# Spartan6-Power.net
KiCad netlist of a schematic drawn in Altium Designer
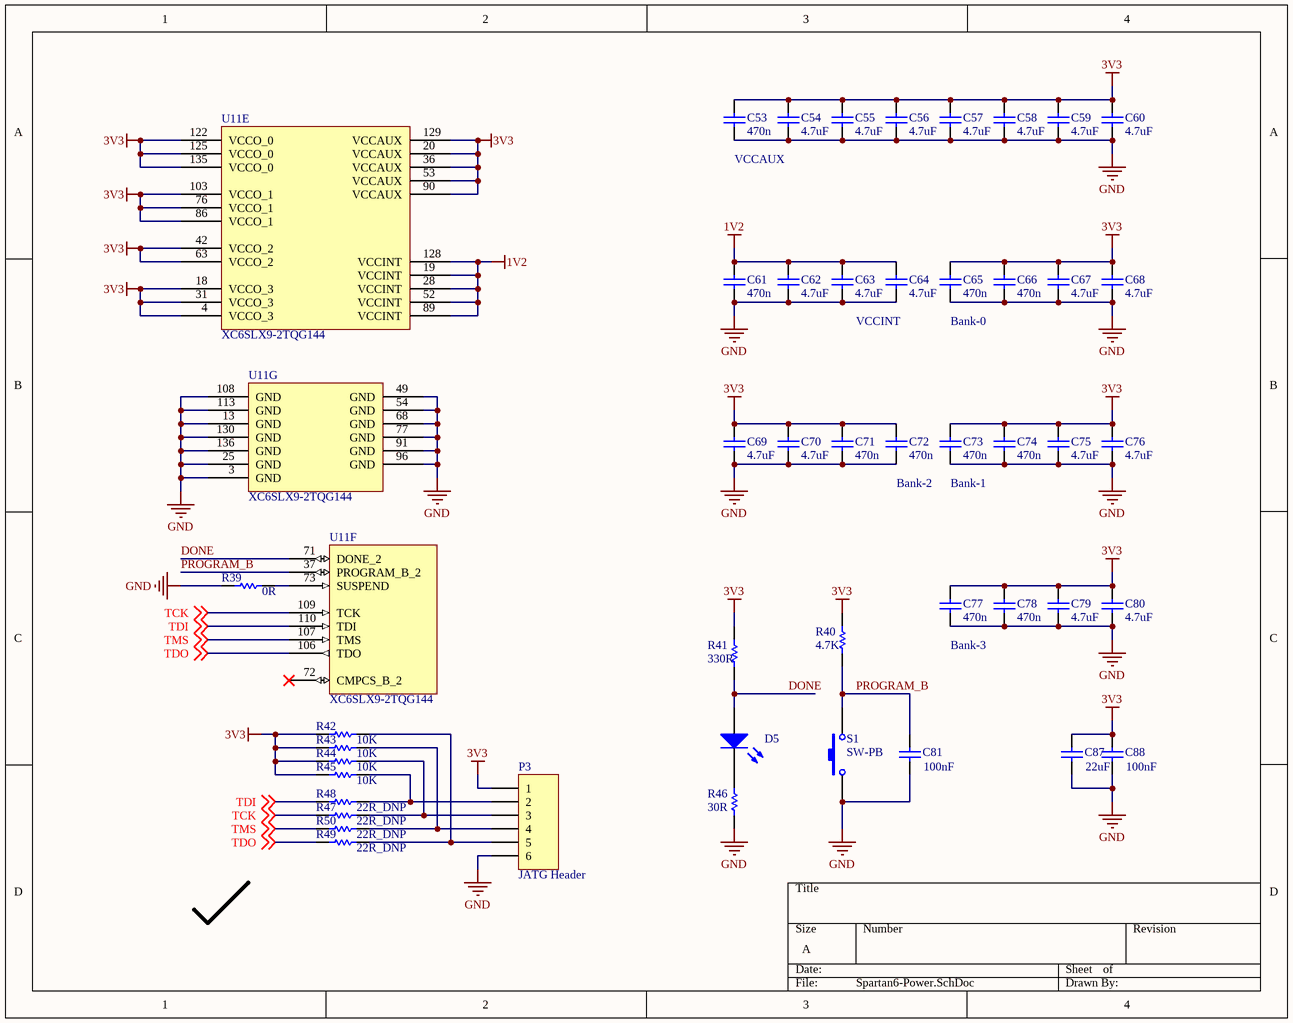
[diagram p0: Spartan6-Power.SchDoc]

(export (version "E")
  (design (tool "Eeschema 10.0.6"))
  (components
    (comp (ref "C53")
      (value "470n")
      (footprint "0402")
      (description "Capacitor (Semiconductor SIM Model)")
      (fields (field (name "Comment") "Cap Semi") (field (name "PUBLISHER") "Altium Limited"))
      (libsource (lib "Miscellaneous Devices") (part "Cap Semi"))
    )
    (comp (ref "C54")
      (value "4.7uF")
      (footprint "0603PKG")
      (description "Capacitor (Semiconductor SIM Model)")
      (fields (field (name "Comment") "Cap Semi") (field (name "PUBLISHER") "Altium Limited"))
      (libsource (lib "Miscellaneous Devices") (part "Cap Semi"))
    )
    (comp (ref "C55")
      (value "4.7uF")
      (footprint "0603PKG")
      (description "Capacitor (Semiconductor SIM Model)")
      (fields (field (name "Comment") "Cap Semi") (field (name "PUBLISHER") "Altium Limited"))
      (libsource (lib "Miscellaneous Devices") (part "Cap Semi"))
    )
    (comp (ref "C56")
      (value "4.7uF")
      (footprint "0603PKG")
      (description "Capacitor (Semiconductor SIM Model)")
      (fields (field (name "Comment") "Cap Semi") (field (name "PUBLISHER") "Altium Limited"))
      (libsource (lib "Miscellaneous Devices") (part "Cap Semi"))
    )
    (comp (ref "C57")
      (value "4.7uF")
      (footprint "0603PKG")
      (description "Capacitor (Semiconductor SIM Model)")
      (fields (field (name "Comment") "Cap Semi") (field (name "PUBLISHER") "Altium Limited"))
      (libsource (lib "Miscellaneous Devices") (part "Cap Semi"))
    )
    (comp (ref "C58")
      (value "4.7uF")
      (footprint "0603PKG")
      (description "Capacitor (Semiconductor SIM Model)")
      (fields (field (name "Comment") "Cap Semi") (field (name "PUBLISHER") "Altium Limited"))
      (libsource (lib "Miscellaneous Devices") (part "Cap Semi"))
    )
    (comp (ref "C59")
      (value "4.7uF")
      (footprint "0603PKG")
      (description "Capacitor (Semiconductor SIM Model)")
      (fields (field (name "Comment") "Cap Semi") (field (name "PUBLISHER") "Altium Limited"))
      (libsource (lib "Miscellaneous Devices") (part "Cap Semi"))
    )
    (comp (ref "C60")
      (value "4.7uF")
      (footprint "0603PKG")
      (description "Capacitor (Semiconductor SIM Model)")
      (fields (field (name "Comment") "Cap Semi") (field (name "PUBLISHER") "Altium Limited"))
      (libsource (lib "Miscellaneous Devices") (part "Cap Semi"))
    )
    (comp (ref "C61")
      (value "470n")
      (footprint "0402")
      (description "Capacitor (Semiconductor SIM Model)")
      (fields (field (name "Comment") "Cap Semi") (field (name "PUBLISHER") "Altium Limited"))
      (libsource (lib "Miscellaneous Devices") (part "Cap Semi"))
    )
    (comp (ref "C62")
      (value "4.7uF")
      (footprint "0603PKG")
      (description "Capacitor (Semiconductor SIM Model)")
      (fields (field (name "Comment") "Cap Semi") (field (name "PUBLISHER") "Altium Limited"))
      (libsource (lib "Miscellaneous Devices") (part "Cap Semi"))
    )
    (comp (ref "C63")
      (value "4.7uF")
      (footprint "0603PKG")
      (description "Capacitor (Semiconductor SIM Model)")
      (fields (field (name "Comment") "Cap Semi") (field (name "PUBLISHER") "Altium Limited"))
      (libsource (lib "Miscellaneous Devices") (part "Cap Semi"))
    )
    (comp (ref "C64")
      (value "4.7uF")
      (footprint "0603PKG")
      (description "Capacitor (Semiconductor SIM Model)")
      (fields (field (name "Comment") "Cap Semi") (field (name "PUBLISHER") "Altium Limited"))
      (libsource (lib "Miscellaneous Devices") (part "Cap Semi"))
    )
    (comp (ref "C65")
      (value "470n")
      (footprint "0402")
      (description "Capacitor (Semiconductor SIM Model)")
      (fields (field (name "Comment") "Cap Semi") (field (name "PUBLISHER") "Altium Limited"))
      (libsource (lib "Miscellaneous Devices") (part "Cap Semi"))
    )
    (comp (ref "C66")
      (value "470n")
      (footprint "0402")
      (description "Capacitor (Semiconductor SIM Model)")
      (fields (field (name "Comment") "Cap Semi") (field (name "PUBLISHER") "Altium Limited"))
      (libsource (lib "Miscellaneous Devices") (part "Cap Semi"))
    )
    (comp (ref "C67")
      (value "4.7uF")
      (footprint "0603PKG")
      (description "Capacitor (Semiconductor SIM Model)")
      (fields (field (name "Comment") "Cap Semi") (field (name "PUBLISHER") "Altium Limited"))
      (libsource (lib "Miscellaneous Devices") (part "Cap Semi"))
    )
    (comp (ref "C68")
      (value "4.7uF")
      (footprint "0603PKG")
      (description "Capacitor (Semiconductor SIM Model)")
      (fields (field (name "Comment") "Cap Semi") (field (name "PUBLISHER") "Altium Limited"))
      (libsource (lib "Miscellaneous Devices") (part "Cap Semi"))
    )
    (comp (ref "C69")
      (value "4.7uF")
      (footprint "0603PKG")
      (description "Capacitor (Semiconductor SIM Model)")
      (fields (field (name "Comment") "Cap Semi") (field (name "PUBLISHER") "Altium Limited"))
      (libsource (lib "Miscellaneous Devices") (part "Cap Semi"))
    )
    (comp (ref "C70")
      (value "4.7uF")
      (footprint "0603PKG")
      (description "Capacitor (Semiconductor SIM Model)")
      (fields (field (name "Comment") "Cap Semi") (field (name "PUBLISHER") "Altium Limited"))
      (libsource (lib "Miscellaneous Devices") (part "Cap Semi"))
    )
    (comp (ref "C71")
      (value "470n")
      (footprint "0402")
      (description "Capacitor (Semiconductor SIM Model)")
      (fields (field (name "Comment") "Cap Semi") (field (name "PUBLISHER") "Altium Limited"))
      (libsource (lib "Miscellaneous Devices") (part "Cap Semi"))
    )
    (comp (ref "C72")
      (value "470n")
      (footprint "0402")
      (description "Capacitor (Semiconductor SIM Model)")
      (fields (field (name "Comment") "Cap Semi") (field (name "PUBLISHER") "Altium Limited"))
      (libsource (lib "Miscellaneous Devices") (part "Cap Semi"))
    )
    (comp (ref "C73")
      (value "470n")
      (footprint "0402")
      (description "Capacitor (Semiconductor SIM Model)")
      (fields (field (name "Comment") "Cap Semi") (field (name "PUBLISHER") "Altium Limited"))
      (libsource (lib "Miscellaneous Devices") (part "Cap Semi"))
    )
    (comp (ref "C74")
      (value "470n")
      (footprint "0402")
      (description "Capacitor (Semiconductor SIM Model)")
      (fields (field (name "Comment") "Cap Semi") (field (name "PUBLISHER") "Altium Limited"))
      (libsource (lib "Miscellaneous Devices") (part "Cap Semi"))
    )
    (comp (ref "C75")
      (value "4.7uF")
      (footprint "0603PKG")
      (description "Capacitor (Semiconductor SIM Model)")
      (fields (field (name "Comment") "Cap Semi") (field (name "PUBLISHER") "Altium Limited"))
      (libsource (lib "Miscellaneous Devices") (part "Cap Semi"))
    )
    (comp (ref "C76")
      (value "4.7uF")
      (footprint "0603PKG")
      (description "Capacitor (Semiconductor SIM Model)")
      (fields (field (name "Comment") "Cap Semi") (field (name "PUBLISHER") "Altium Limited"))
      (libsource (lib "Miscellaneous Devices") (part "Cap Semi"))
    )
    (comp (ref "C77")
      (value "470n")
      (footprint "0402")
      (description "Capacitor (Semiconductor SIM Model)")
      (fields (field (name "Comment") "Cap Semi") (field (name "PUBLISHER") "Altium Limited"))
      (libsource (lib "Miscellaneous Devices") (part "Cap Semi"))
    )
    (comp (ref "C78")
      (value "470n")
      (footprint "0402")
      (description "Capacitor (Semiconductor SIM Model)")
      (fields (field (name "Comment") "Cap Semi") (field (name "PUBLISHER") "Altium Limited"))
      (libsource (lib "Miscellaneous Devices") (part "Cap Semi"))
    )
    (comp (ref "C79")
      (value "4.7uF")
      (footprint "0603PKG")
      (description "Capacitor (Semiconductor SIM Model)")
      (fields (field (name "Comment") "Cap Semi") (field (name "PUBLISHER") "Altium Limited"))
      (libsource (lib "Miscellaneous Devices") (part "Cap Semi"))
    )
    (comp (ref "C80")
      (value "4.7uF")
      (footprint "0603PKG")
      (description "Capacitor (Semiconductor SIM Model)")
      (fields (field (name "Comment") "Cap Semi") (field (name "PUBLISHER") "Altium Limited"))
      (libsource (lib "Miscellaneous Devices") (part "Cap Semi"))
    )
    (comp (ref "C81")
      (value "100nF")
      (footprint "C0805")
      (description "Capacitor")
      (fields (field (name "Comment") "Cap") (field (name "PUBLISHER") "Altium Limited"))
      (libsource (lib "Miscellaneous Devices") (part "Cap"))
    )
    (comp (ref "C87")
      (value "22uF")
      (footprint "C1206")
      (description "Capacitor")
      (fields (field (name "Comment") "Cap") (field (name "PUBLISHER") "Altium Limited"))
      (libsource (lib "Miscellaneous Devices") (part "Cap"))
    )
    (comp (ref "C88")
      (value "100nF")
      (footprint "C0805")
      (description "Capacitor")
      (fields (field (name "Comment") "Cap") (field (name "PUBLISHER") "Altium Limited"))
      (libsource (lib "Miscellaneous Devices") (part "Cap"))
    )
    (comp (ref "D5")
      (value "LED0")
      (footprint "C0805")
      (description "Typical INFRARED GaAs LED")
      (fields (field (name "PUBLISHER") "Altium Limited"))
      (libsource (lib "Miscellaneous Devices") (part "LED0"))
    )
    (comp (ref "P3")
      (value "JATG Header")
      (footprint "HDR1X6")
      (description "Header, 6-Pin")
      (fields (field (name "PUBLISHER") "Altium Limited"))
      (libsource (lib "Miscellaneous Connectors") (part "Header 6"))
    )
    (comp (ref "R39")
      (value "0R")
      (footprint "0603PKG")
      (description "Resistor")
      (fields (field (name "Comment") "Res1") (field (name "PUBLISHER") "Altium Limited"))
      (libsource (lib "Miscellaneous Devices") (part "Res1"))
    )
    (comp (ref "R40")
      (value "4.7K")
      (footprint "0603PKG")
      (description "Resistor")
      (fields (field (name "Comment") "Res1") (field (name "PUBLISHER") "Altium Limited"))
      (libsource (lib "Miscellaneous Devices") (part "Res1"))
    )
    (comp (ref "R41")
      (value "330R")
      (footprint "0603PKG")
      (description "Resistor")
      (fields (field (name "Comment") "Res1") (field (name "PUBLISHER") "Altium Limited"))
      (libsource (lib "Miscellaneous Devices") (part "Res1"))
    )
    (comp (ref "R42")
      (value "10K")
      (footprint "0603PKG")
      (description "Semiconductor Resistor")
      (fields (field (name "Comment") "Res Semi") (field (name "PUBLISHER") "Altium Limited"))
      (libsource (lib "Miscellaneous Devices") (part "Res Semi"))
    )
    (comp (ref "R43")
      (value "10K")
      (footprint "0603PKG")
      (description "Semiconductor Resistor")
      (fields (field (name "Comment") "Res Semi") (field (name "PUBLISHER") "Altium Limited"))
      (libsource (lib "Miscellaneous Devices") (part "Res Semi"))
    )
    (comp (ref "R44")
      (value "10K")
      (footprint "0603PKG")
      (description "Semiconductor Resistor")
      (fields (field (name "Comment") "Res Semi") (field (name "PUBLISHER") "Altium Limited"))
      (libsource (lib "Miscellaneous Devices") (part "Res Semi"))
    )
    (comp (ref "R45")
      (value "10K")
      (footprint "0603PKG")
      (description "Semiconductor Resistor")
      (fields (field (name "Comment") "Res Semi") (field (name "PUBLISHER") "Altium Limited"))
      (libsource (lib "Miscellaneous Devices") (part "Res Semi"))
    )
    (comp (ref "R46")
      (value "30R")
      (footprint "0603PKG")
      (description "Resistor")
      (fields (field (name "Comment") "Res1") (field (name "PUBLISHER") "Altium Limited"))
      (libsource (lib "Miscellaneous Devices") (part "Res1"))
    )
    (comp (ref "R47")
      (value "22R_DNP")
      (footprint "0603PKG")
      (description "Semiconductor Resistor")
      (fields (field (name "Comment") "Res Semi") (field (name "PUBLISHER") "Altium Limited"))
      (libsource (lib "Miscellaneous Devices") (part "Res Semi"))
    )
    (comp (ref "R48")
      (value "22R_DNP")
      (footprint "0603PKG")
      (description "Semiconductor Resistor")
      (fields (field (name "Comment") "Res Semi") (field (name "PUBLISHER") "Altium Limited"))
      (libsource (lib "Miscellaneous Devices") (part "Res Semi"))
    )
    (comp (ref "R49")
      (value "22R_DNP")
      (footprint "0603PKG")
      (description "Semiconductor Resistor")
      (fields (field (name "Comment") "Res Semi") (field (name "PUBLISHER") "Altium Limited"))
      (libsource (lib "Miscellaneous Devices") (part "Res Semi"))
    )
    (comp (ref "R50")
      (value "22R_DNP")
      (footprint "0603PKG")
      (description "Semiconductor Resistor")
      (fields (field (name "Comment") "Res Semi") (field (name "PUBLISHER") "Altium Limited"))
      (libsource (lib "Miscellaneous Devices") (part "Res Semi"))
    )
    (comp (ref "S1")
      (value "SW-PB")
      (footprint "SMD push button")
      (description "Switch")
      (fields (field (name "PUBLISHER") "Altium Limited"))
      (libsource (lib "Miscellaneous Devices") (part "SW-PB"))
    )
    (comp (ref "U11")
      (value "XC6SLX9-2TQG144")
      (footprint "TQG144")
      (description "Xilinx Spartan6 LX9")
      (libsource (lib "Connector_IntLib") (part "XC6SLX9-2TQG144C"))
    )
  )
  (nets
    (net (code "1") (name "/DONE") (class "Default")
      (node (ref "D5") (pin "1") (pinfunction "A_1") (pintype "passive"))
      (node (ref "R41") (pin "1") (pinfunction "1_1") (pintype "passive"))
      (node (ref "U11") (pin "71") (pinfunction "DONE_2_71") (pintype "bidirectional"))
    )
    (net (code "2") (name "/PROGRAM_B") (class "Default")
      (node (ref "C81") (pin "2") (pinfunction "2_2") (pintype "passive"))
      (node (ref "R40") (pin "1") (pinfunction "1_1") (pintype "passive"))
      (node (ref "S1") (pin "2") (pinfunction "2_2") (pintype "passive"))
      (node (ref "U11") (pin "37") (pinfunction "PROGRAM_B_2_37") (pintype "bidirectional"))
    )
    (net (code "3") (name "1V2") (class "Default")
      (node (ref "C61") (pin "1") (pinfunction "1_1") (pintype "passive"))
      (node (ref "C62") (pin "1") (pinfunction "1_1") (pintype "passive"))
      (node (ref "C63") (pin "1") (pinfunction "1_1") (pintype "passive"))
      (node (ref "C64") (pin "1") (pinfunction "1_1") (pintype "passive"))
      (node (ref "U11") (pin "128") (pinfunction "VCCINT_128") (pintype "power_in"))
      (node (ref "U11") (pin "19") (pinfunction "VCCINT_19") (pintype "power_in"))
      (node (ref "U11") (pin "28") (pinfunction "VCCINT_28") (pintype "power_in"))
      (node (ref "U11") (pin "52") (pinfunction "VCCINT_52") (pintype "power_in"))
      (node (ref "U11") (pin "89") (pinfunction "VCCINT_89") (pintype "power_in"))
    )
    (net (code "4") (name "3V3") (class "Default")
      (node (ref "C53") (pin "1") (pinfunction "1_1") (pintype "passive"))
      (node (ref "C54") (pin "1") (pinfunction "1_1") (pintype "passive"))
      (node (ref "C55") (pin "1") (pinfunction "1_1") (pintype "passive"))
      (node (ref "C56") (pin "1") (pinfunction "1_1") (pintype "passive"))
      (node (ref "C57") (pin "1") (pinfunction "1_1") (pintype "passive"))
      (node (ref "C58") (pin "1") (pinfunction "1_1") (pintype "passive"))
      (node (ref "C59") (pin "1") (pinfunction "1_1") (pintype "passive"))
      (node (ref "C60") (pin "1") (pinfunction "1_1") (pintype "passive"))
      (node (ref "C65") (pin "1") (pinfunction "1_1") (pintype "passive"))
      (node (ref "C66") (pin "1") (pinfunction "1_1") (pintype "passive"))
      (node (ref "C67") (pin "1") (pinfunction "1_1") (pintype "passive"))
      (node (ref "C68") (pin "1") (pinfunction "1_1") (pintype "passive"))
      (node (ref "C69") (pin "1") (pinfunction "1_1") (pintype "passive"))
      (node (ref "C70") (pin "1") (pinfunction "1_1") (pintype "passive"))
      (node (ref "C71") (pin "1") (pinfunction "1_1") (pintype "passive"))
      (node (ref "C72") (pin "1") (pinfunction "1_1") (pintype "passive"))
      (node (ref "C73") (pin "1") (pinfunction "1_1") (pintype "passive"))
      (node (ref "C74") (pin "1") (pinfunction "1_1") (pintype "passive"))
      (node (ref "C75") (pin "1") (pinfunction "1_1") (pintype "passive"))
      (node (ref "C76") (pin "1") (pinfunction "1_1") (pintype "passive"))
      (node (ref "C77") (pin "1") (pinfunction "1_1") (pintype "passive"))
      (node (ref "C78") (pin "1") (pinfunction "1_1") (pintype "passive"))
      (node (ref "C79") (pin "1") (pinfunction "1_1") (pintype "passive"))
      (node (ref "C80") (pin "1") (pinfunction "1_1") (pintype "passive"))
      (node (ref "C87") (pin "2") (pinfunction "2_2") (pintype "passive"))
      (node (ref "C88") (pin "2") (pinfunction "2_2") (pintype "passive"))
      (node (ref "P3") (pin "1") (pinfunction "1_1") (pintype "passive"))
      (node (ref "R40") (pin "2") (pinfunction "2_2") (pintype "passive"))
      (node (ref "R41") (pin "2") (pinfunction "2_2") (pintype "passive"))
      (node (ref "R42") (pin "2") (pinfunction "2_2") (pintype "passive"))
      (node (ref "R43") (pin "2") (pinfunction "2_2") (pintype "passive"))
      (node (ref "R44") (pin "2") (pinfunction "2_2") (pintype "passive"))
      (node (ref "R45") (pin "2") (pinfunction "2_2") (pintype "passive"))
      (node (ref "U11") (pin "103") (pinfunction "VCCO_1_103") (pintype "power_in"))
      (node (ref "U11") (pin "122") (pinfunction "VCCO_0_122") (pintype "power_in"))
      (node (ref "U11") (pin "125") (pinfunction "VCCO_0_125") (pintype "power_in"))
      (node (ref "U11") (pin "129") (pinfunction "VCCAUX_129") (pintype "power_in"))
      (node (ref "U11") (pin "135") (pinfunction "VCCO_0_135") (pintype "power_in"))
      (node (ref "U11") (pin "18") (pinfunction "VCCO_3_18") (pintype "power_in"))
      (node (ref "U11") (pin "20") (pinfunction "VCCAUX_20") (pintype "power_in"))
      (node (ref "U11") (pin "31") (pinfunction "VCCO_3_31") (pintype "power_in"))
      (node (ref "U11") (pin "36") (pinfunction "VCCAUX_36") (pintype "power_in"))
      (node (ref "U11") (pin "4") (pinfunction "VCCO_3_4") (pintype "power_in"))
      (node (ref "U11") (pin "42") (pinfunction "VCCO_2_42") (pintype "power_in"))
      (node (ref "U11") (pin "53") (pinfunction "VCCAUX_53") (pintype "power_in"))
      (node (ref "U11") (pin "63") (pinfunction "VCCO_2_63") (pintype "power_in"))
      (node (ref "U11") (pin "76") (pinfunction "VCCO_1_76") (pintype "power_in"))
      (node (ref "U11") (pin "86") (pinfunction "VCCO_1_86") (pintype "power_in"))
      (node (ref "U11") (pin "90") (pinfunction "VCCAUX_90") (pintype "power_in"))
    )
    (net (code "5") (name "GND") (class "Default")
      (node (ref "C53") (pin "2") (pinfunction "2_2") (pintype "passive"))
      (node (ref "C54") (pin "2") (pinfunction "2_2") (pintype "passive"))
      (node (ref "C55") (pin "2") (pinfunction "2_2") (pintype "passive"))
      (node (ref "C56") (pin "2") (pinfunction "2_2") (pintype "passive"))
      (node (ref "C57") (pin "2") (pinfunction "2_2") (pintype "passive"))
      (node (ref "C58") (pin "2") (pinfunction "2_2") (pintype "passive"))
      (node (ref "C59") (pin "2") (pinfunction "2_2") (pintype "passive"))
      (node (ref "C60") (pin "2") (pinfunction "2_2") (pintype "passive"))
      (node (ref "C61") (pin "2") (pinfunction "2_2") (pintype "passive"))
      (node (ref "C62") (pin "2") (pinfunction "2_2") (pintype "passive"))
      (node (ref "C63") (pin "2") (pinfunction "2_2") (pintype "passive"))
      (node (ref "C64") (pin "2") (pinfunction "2_2") (pintype "passive"))
      (node (ref "C65") (pin "2") (pinfunction "2_2") (pintype "passive"))
      (node (ref "C66") (pin "2") (pinfunction "2_2") (pintype "passive"))
      (node (ref "C67") (pin "2") (pinfunction "2_2") (pintype "passive"))
      (node (ref "C68") (pin "2") (pinfunction "2_2") (pintype "passive"))
      (node (ref "C69") (pin "2") (pinfunction "2_2") (pintype "passive"))
      (node (ref "C70") (pin "2") (pinfunction "2_2") (pintype "passive"))
      (node (ref "C71") (pin "2") (pinfunction "2_2") (pintype "passive"))
      (node (ref "C72") (pin "2") (pinfunction "2_2") (pintype "passive"))
      (node (ref "C73") (pin "2") (pinfunction "2_2") (pintype "passive"))
      (node (ref "C74") (pin "2") (pinfunction "2_2") (pintype "passive"))
      (node (ref "C75") (pin "2") (pinfunction "2_2") (pintype "passive"))
      (node (ref "C76") (pin "2") (pinfunction "2_2") (pintype "passive"))
      (node (ref "C77") (pin "2") (pinfunction "2_2") (pintype "passive"))
      (node (ref "C78") (pin "2") (pinfunction "2_2") (pintype "passive"))
      (node (ref "C79") (pin "2") (pinfunction "2_2") (pintype "passive"))
      (node (ref "C80") (pin "2") (pinfunction "2_2") (pintype "passive"))
      (node (ref "C81") (pin "1") (pinfunction "1_1") (pintype "passive"))
      (node (ref "C87") (pin "1") (pinfunction "1_1") (pintype "passive"))
      (node (ref "C88") (pin "1") (pinfunction "1_1") (pintype "passive"))
      (node (ref "P3") (pin "6") (pinfunction "6_6") (pintype "passive"))
      (node (ref "R39") (pin "1") (pinfunction "1_1") (pintype "passive"))
      (node (ref "R46") (pin "1") (pinfunction "1_1") (pintype "passive"))
      (node (ref "S1") (pin "1") (pinfunction "1_1") (pintype "passive"))
      (node (ref "U11") (pin "108") (pinfunction "GND_108") (pintype "power_in"))
      (node (ref "U11") (pin "113") (pinfunction "GND_113") (pintype "power_in"))
      (node (ref "U11") (pin "13") (pinfunction "GND_13") (pintype "power_in"))
      (node (ref "U11") (pin "130") (pinfunction "GND_130") (pintype "power_in"))
      (node (ref "U11") (pin "136") (pinfunction "GND_136") (pintype "power_in"))
      (node (ref "U11") (pin "25") (pinfunction "GND_25") (pintype "power_in"))
      (node (ref "U11") (pin "3") (pinfunction "GND_3") (pintype "power_in"))
      (node (ref "U11") (pin "49") (pinfunction "GND_49") (pintype "power_in"))
      (node (ref "U11") (pin "54") (pinfunction "GND_54") (pintype "power_in"))
      (node (ref "U11") (pin "68") (pinfunction "GND_68") (pintype "power_in"))
      (node (ref "U11") (pin "77") (pinfunction "GND_77") (pintype "power_in"))
      (node (ref "U11") (pin "91") (pinfunction "GND_91") (pintype "power_in"))
      (node (ref "U11") (pin "96") (pinfunction "GND_96") (pintype "power_in"))
    )
    (net (code "6") (name "Net-(D5-K)") (class "Default")
      (node (ref "D5") (pin "2") (pinfunction "K_2") (pintype "passive"))
      (node (ref "R46") (pin "2") (pinfunction "2_2") (pintype "passive"))
    )
    (net (code "7") (name "Net-(P3-Pad2)") (class "Default")
      (node (ref "P3") (pin "2") (pinfunction "2_2") (pintype "passive"))
      (node (ref "R45") (pin "1") (pinfunction "1_1") (pintype "passive"))
      (node (ref "R48") (pin "1") (pinfunction "1_1") (pintype "passive"))
    )
    (net (code "8") (name "Net-(P3-Pad3)") (class "Default")
      (node (ref "P3") (pin "3") (pinfunction "3_3") (pintype "passive"))
      (node (ref "R44") (pin "1") (pinfunction "1_1") (pintype "passive"))
      (node (ref "R47") (pin "1") (pinfunction "1_1") (pintype "passive"))
    )
    (net (code "9") (name "Net-(P3-Pad4)") (class "Default")
      (node (ref "P3") (pin "4") (pinfunction "4_4") (pintype "passive"))
      (node (ref "R43") (pin "1") (pinfunction "1_1") (pintype "passive"))
      (node (ref "R50") (pin "1") (pinfunction "1_1") (pintype "passive"))
    )
    (net (code "10") (name "Net-(P3-Pad5)") (class "Default")
      (node (ref "P3") (pin "5") (pinfunction "5_5") (pintype "passive"))
      (node (ref "R42") (pin "1") (pinfunction "1_1") (pintype "passive"))
      (node (ref "R49") (pin "1") (pinfunction "1_1") (pintype "passive"))
    )
    (net (code "11") (name "Net-(U11F-SUSPEND)") (class "Default")
      (node (ref "R39") (pin "2") (pinfunction "2_2") (pintype "passive"))
      (node (ref "U11") (pin "73") (pinfunction "SUSPEND_73") (pintype "input"))
    )
    (net (code "12") (name "TCK") (class "Default")
      (node (ref "R47") (pin "2") (pinfunction "2_2") (pintype "passive"))
      (node (ref "U11") (pin "109") (pinfunction "TCK_109") (pintype "input"))
    )
    (net (code "13") (name "TDI") (class "Default")
      (node (ref "R48") (pin "2") (pinfunction "2_2") (pintype "passive"))
      (node (ref "U11") (pin "110") (pinfunction "TDI_110") (pintype "input"))
    )
    (net (code "14") (name "TDO") (class "Default")
      (node (ref "R49") (pin "2") (pinfunction "2_2") (pintype "passive"))
      (node (ref "U11") (pin "106") (pinfunction "TDO_106") (pintype "output"))
    )
    (net (code "15") (name "TMS") (class "Default")
      (node (ref "R50") (pin "2") (pinfunction "2_2") (pintype "passive"))
      (node (ref "U11") (pin "107") (pinfunction "TMS_107") (pintype "input"))
    )
    (net (code "16") (name "unconnected-(U11F-CMPCS_B_2-Pad72)") (class "Default")
      (node (ref "U11") (pin "72") (pinfunction "CMPCS_B_2_72") (pintype "bidirectional+no_connect"))
    )
  )
)
